# self_balancing_robot.net
KiCad netlist of a schematic drawn in EasyEDA Pro
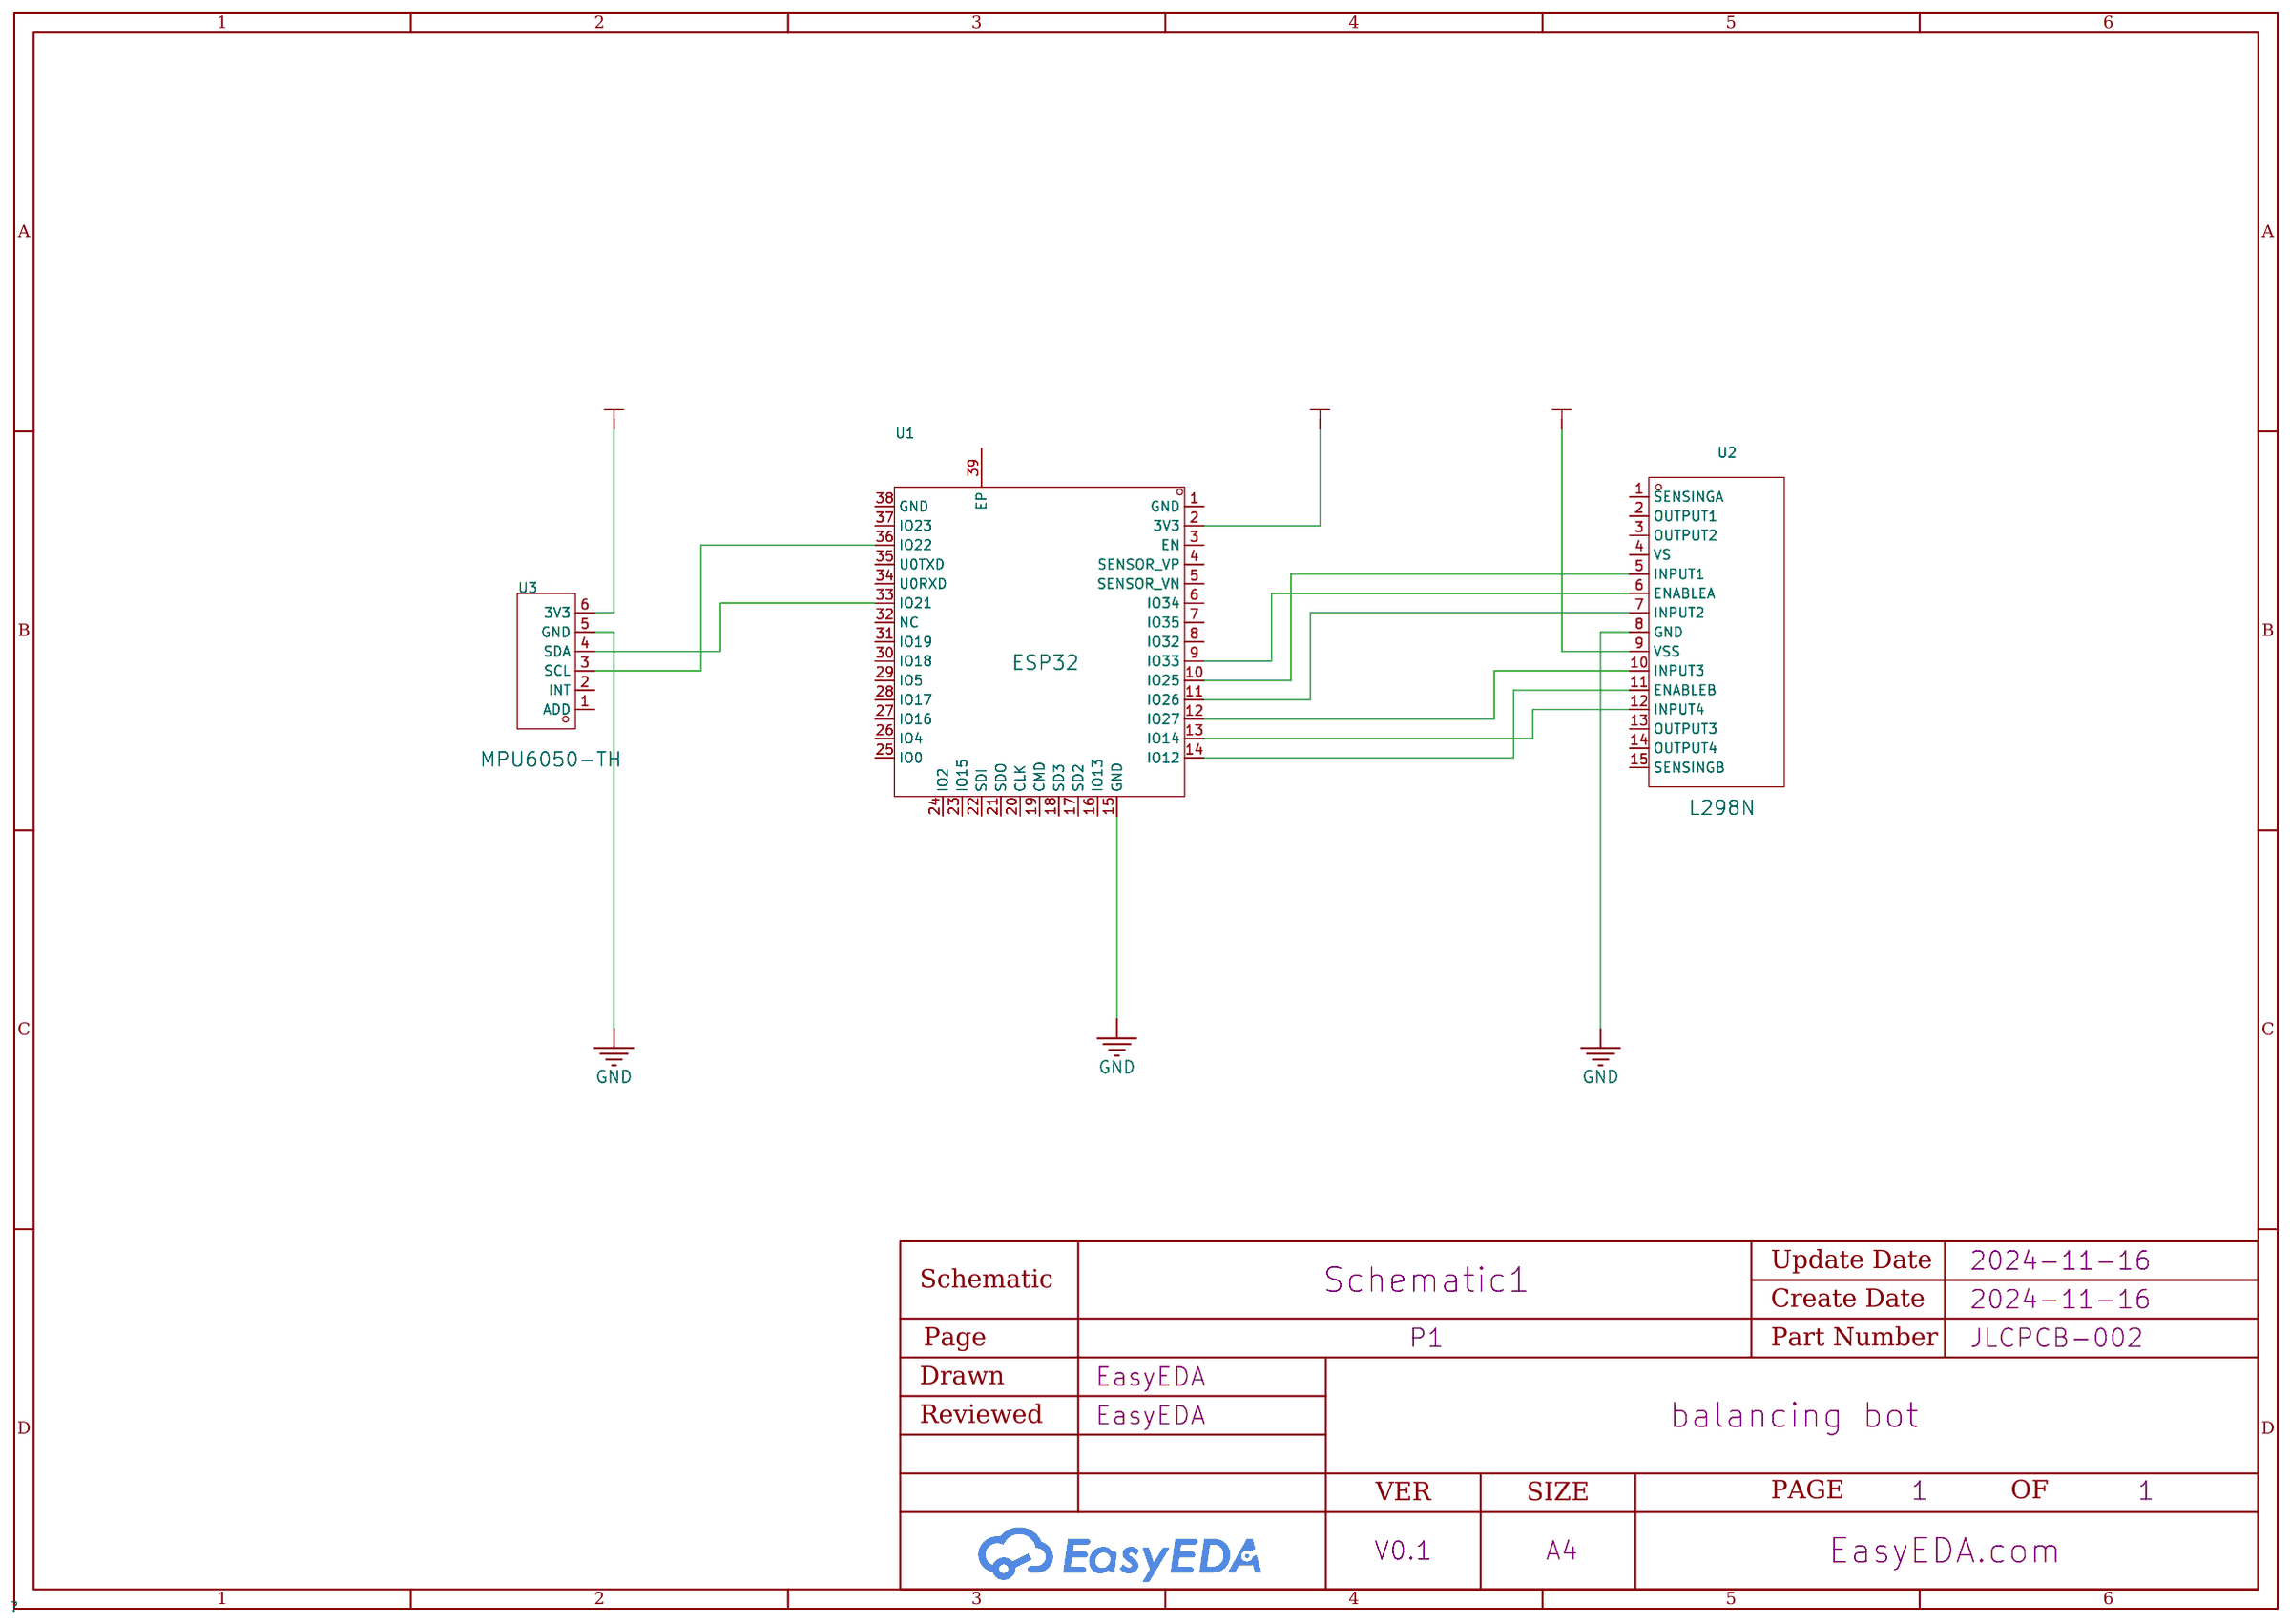
[diagram p0: schematic sheet]

(export (version "E")
  (design (tool "Eeschema 10.0.6"))
  (components
    (comp (ref "U1")
      (value "2.4GHz")
      (footprint "easyedapro:WIRELM-SMD_ESP32-S")
      (fields (field (name "Manufacturer Part") "ESP32-S") (field (name "Manufacturer") "Ai-Thinker(安信可)"))
      (libsource (lib "easyedapro") (part "ESP32-S"))
    )
    (comp (ref "U2")
      (value "L298N")
      (footprint "easyedapro:MULTIWATT-15_L19.6-W5.0-P1.27-L")
      (libsource (lib "easyedapro") (part "L298N_C504386"))
    )
    (comp (ref "U3")
      (value "MPU6050-TH")
      (footprint "easyedapro:COMM-TH_MPU6050-TH")
      (libsource (lib "easyedapro") (part "MPU6050-TH"))
    )
  )
  (nets
    (net (code "1") (name "3.3V") (class "Default")
      (node (ref "U1") (pin "2") (pinfunction "3V3_2") (pintype "input"))
      (node (ref "U3") (pin "6") (pinfunction "3V3_6") (pintype "unspecified"))
    )
    (net (code "2") (name "7.4V") (class "Default")
      (node (ref "U2") (pin "9") (pinfunction "VSS_9") (pintype "unspecified"))
    )
    (net (code "3") (name "GND") (class "Default")
      (node (ref "U1") (pin "15") (pinfunction "GND_15") (pintype "input"))
      (node (ref "U2") (pin "8") (pinfunction "GND_8") (pintype "unspecified"))
      (node (ref "U3") (pin "5") (pinfunction "GND_5") (pintype "unspecified"))
    )
    (net (code "4") (name "Net-(U1-IO12)") (class "Default")
      (node (ref "U1") (pin "14") (pinfunction "IO12_14") (pintype "input"))
      (node (ref "U2") (pin "11") (pinfunction "ENABLEB_11") (pintype "unspecified"))
    )
    (net (code "5") (name "Net-(U1-IO14)") (class "Default")
      (node (ref "U1") (pin "13") (pinfunction "IO14_13") (pintype "input"))
      (node (ref "U2") (pin "12") (pinfunction "INPUT4_12") (pintype "unspecified"))
    )
    (net (code "6") (name "Net-(U1-IO21)") (class "Default")
      (node (ref "U1") (pin "33") (pinfunction "IO21_33") (pintype "input"))
      (node (ref "U3") (pin "4") (pinfunction "SDA_4") (pintype "unspecified"))
    )
    (net (code "7") (name "Net-(U1-IO22)") (class "Default")
      (node (ref "U1") (pin "36") (pinfunction "IO22_36") (pintype "input"))
      (node (ref "U3") (pin "3") (pinfunction "SCL_3") (pintype "unspecified"))
    )
    (net (code "8") (name "Net-(U1-IO25)") (class "Default")
      (node (ref "U1") (pin "10") (pinfunction "IO25_10") (pintype "input"))
      (node (ref "U2") (pin "5") (pinfunction "INPUT1_5") (pintype "unspecified"))
    )
    (net (code "9") (name "Net-(U1-IO26)") (class "Default")
      (node (ref "U1") (pin "11") (pinfunction "IO26_11") (pintype "input"))
      (node (ref "U2") (pin "7") (pinfunction "INPUT2_7") (pintype "unspecified"))
    )
    (net (code "10") (name "Net-(U1-IO27)") (class "Default")
      (node (ref "U1") (pin "12") (pinfunction "IO27_12") (pintype "input"))
      (node (ref "U2") (pin "10") (pinfunction "INPUT3_10") (pintype "unspecified"))
    )
    (net (code "11") (name "Net-(U1-IO33)") (class "Default")
      (node (ref "U1") (pin "9") (pinfunction "IO33_9") (pintype "input"))
      (node (ref "U2") (pin "6") (pinfunction "ENABLEA_6") (pintype "unspecified"))
    )
    (net (code "12") (name "unconnected-(U1-CLK-Pad20)") (class "Default")
      (node (ref "U1") (pin "20") (pinfunction "CLK_20") (pintype "input"))
    )
    (net (code "13") (name "unconnected-(U1-CMD-Pad19)") (class "Default")
      (node (ref "U1") (pin "19") (pinfunction "CMD_19") (pintype "input"))
    )
    (net (code "14") (name "unconnected-(U1-EN-Pad3)") (class "Default")
      (node (ref "U1") (pin "3") (pinfunction "EN_3") (pintype "input"))
    )
    (net (code "15") (name "unconnected-(U1-EP-Pad39)") (class "Default")
      (node (ref "U1") (pin "39") (pinfunction "EP_39") (pintype "input"))
    )
    (net (code "16") (name "unconnected-(U1-GND-Pad1)") (class "Default")
      (node (ref "U1") (pin "1") (pinfunction "GND_1") (pintype "input"))
    )
    (net (code "17") (name "unconnected-(U1-GND-Pad38)") (class "Default")
      (node (ref "U1") (pin "38") (pinfunction "GND_38") (pintype "input"))
    )
    (net (code "18") (name "unconnected-(U1-IO0-Pad25)") (class "Default")
      (node (ref "U1") (pin "25") (pinfunction "IO0_25") (pintype "input"))
    )
    (net (code "19") (name "unconnected-(U1-IO2-Pad24)") (class "Default")
      (node (ref "U1") (pin "24") (pinfunction "IO2_24") (pintype "input"))
    )
    (net (code "20") (name "unconnected-(U1-IO4-Pad26)") (class "Default")
      (node (ref "U1") (pin "26") (pinfunction "IO4_26") (pintype "input"))
    )
    (net (code "21") (name "unconnected-(U1-IO5-Pad29)") (class "Default")
      (node (ref "U1") (pin "29") (pinfunction "IO5_29") (pintype "input"))
    )
    (net (code "22") (name "unconnected-(U1-IO13-Pad16)") (class "Default")
      (node (ref "U1") (pin "16") (pinfunction "IO13_16") (pintype "input"))
    )
    (net (code "23") (name "unconnected-(U1-IO15-Pad23)") (class "Default")
      (node (ref "U1") (pin "23") (pinfunction "IO15_23") (pintype "input"))
    )
    (net (code "24") (name "unconnected-(U1-IO16-Pad27)") (class "Default")
      (node (ref "U1") (pin "27") (pinfunction "IO16_27") (pintype "input"))
    )
    (net (code "25") (name "unconnected-(U1-IO17-Pad28)") (class "Default")
      (node (ref "U1") (pin "28") (pinfunction "IO17_28") (pintype "input"))
    )
    (net (code "26") (name "unconnected-(U1-IO18-Pad30)") (class "Default")
      (node (ref "U1") (pin "30") (pinfunction "IO18_30") (pintype "input"))
    )
    (net (code "27") (name "unconnected-(U1-IO19-Pad31)") (class "Default")
      (node (ref "U1") (pin "31") (pinfunction "IO19_31") (pintype "input"))
    )
    (net (code "28") (name "unconnected-(U1-IO23-Pad37)") (class "Default")
      (node (ref "U1") (pin "37") (pinfunction "IO23_37") (pintype "input"))
    )
    (net (code "29") (name "unconnected-(U1-IO32-Pad8)") (class "Default")
      (node (ref "U1") (pin "8") (pinfunction "IO32_8") (pintype "input"))
    )
    (net (code "30") (name "unconnected-(U1-IO34-Pad6)") (class "Default")
      (node (ref "U1") (pin "6") (pinfunction "IO34_6") (pintype "input"))
    )
    (net (code "31") (name "unconnected-(U1-IO35-Pad7)") (class "Default")
      (node (ref "U1") (pin "7") (pinfunction "IO35_7") (pintype "input"))
    )
    (net (code "32") (name "unconnected-(U1-NC-Pad32)") (class "Default")
      (node (ref "U1") (pin "32") (pinfunction "NC_32") (pintype "input"))
    )
    (net (code "33") (name "unconnected-(U1-SD2-Pad17)") (class "Default")
      (node (ref "U1") (pin "17") (pinfunction "SD2_17") (pintype "input"))
    )
    (net (code "34") (name "unconnected-(U1-SD3-Pad18)") (class "Default")
      (node (ref "U1") (pin "18") (pinfunction "SD3_18") (pintype "input"))
    )
    (net (code "35") (name "unconnected-(U1-SDI-Pad22)") (class "Default")
      (node (ref "U1") (pin "22") (pinfunction "SDI_22") (pintype "input"))
    )
    (net (code "36") (name "unconnected-(U1-SDO-Pad21)") (class "Default")
      (node (ref "U1") (pin "21") (pinfunction "SDO_21") (pintype "input"))
    )
    (net (code "37") (name "unconnected-(U1-SENSOR_VN-Pad5)") (class "Default")
      (node (ref "U1") (pin "5") (pinfunction "SENSOR_VN_5") (pintype "input"))
    )
    (net (code "38") (name "unconnected-(U1-SENSOR_VP-Pad4)") (class "Default")
      (node (ref "U1") (pin "4") (pinfunction "SENSOR_VP_4") (pintype "input"))
    )
    (net (code "39") (name "unconnected-(U1-U0RXD-Pad34)") (class "Default")
      (node (ref "U1") (pin "34") (pinfunction "U0RXD_34") (pintype "input"))
    )
    (net (code "40") (name "unconnected-(U1-U0TXD-Pad35)") (class "Default")
      (node (ref "U1") (pin "35") (pinfunction "U0TXD_35") (pintype "input"))
    )
    (net (code "41") (name "unconnected-(U2-OUTPUT1-Pad2)") (class "Default")
      (node (ref "U2") (pin "2") (pinfunction "OUTPUT1_2") (pintype "unspecified"))
    )
    (net (code "42") (name "unconnected-(U2-OUTPUT2-Pad3)") (class "Default")
      (node (ref "U2") (pin "3") (pinfunction "OUTPUT2_3") (pintype "unspecified"))
    )
    (net (code "43") (name "unconnected-(U2-OUTPUT3-Pad13)") (class "Default")
      (node (ref "U2") (pin "13") (pinfunction "OUTPUT3_13") (pintype "unspecified"))
    )
    (net (code "44") (name "unconnected-(U2-OUTPUT4-Pad14)") (class "Default")
      (node (ref "U2") (pin "14") (pinfunction "OUTPUT4_14") (pintype "unspecified"))
    )
    (net (code "45") (name "unconnected-(U2-SENSINGA-Pad1)") (class "Default")
      (node (ref "U2") (pin "1") (pinfunction "SENSINGA_1") (pintype "unspecified"))
    )
    (net (code "46") (name "unconnected-(U2-SENSINGB-Pad15)") (class "Default")
      (node (ref "U2") (pin "15") (pinfunction "SENSINGB_15") (pintype "unspecified"))
    )
    (net (code "47") (name "unconnected-(U2-VS-Pad4)") (class "Default")
      (node (ref "U2") (pin "4") (pinfunction "VS_4") (pintype "unspecified"))
    )
    (net (code "48") (name "unconnected-(U3-ADD-Pad1)") (class "Default")
      (node (ref "U3") (pin "1") (pinfunction "ADD_1") (pintype "unspecified"))
    )
    (net (code "49") (name "unconnected-(U3-INT-Pad2)") (class "Default")
      (node (ref "U3") (pin "2") (pinfunction "INT_2") (pintype "unspecified"))
    )
  )
)
